# Op-amp_Microphone_Preamp.net
KiCad netlist of a schematic drawn in EAGLE
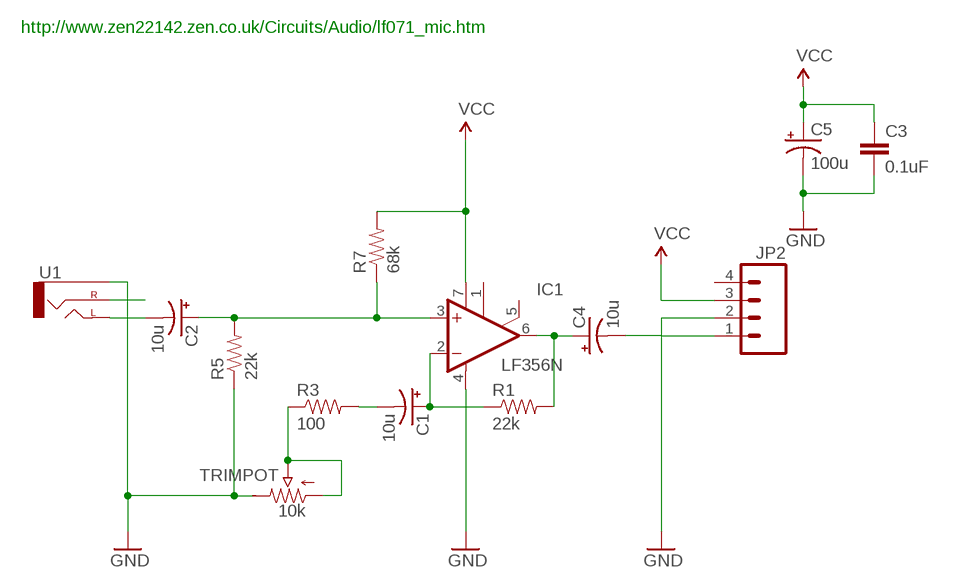
[diagram p0: schematic, sheet 1]

(export (version "E")
  (design (tool "Eeschema 10.0.6"))
  (components
    (comp (ref "C1")
      (value "10u")
      (footprint "eagle-import:CPOL-RADIAL-100UF-25V")
      (libsource (lib "eagle-import") (part "CAP_POLPTH1"))
    )
    (comp (ref "C2")
      (value "10u")
      (footprint "eagle-import:CPOL-RADIAL-100UF-25V")
      (libsource (lib "eagle-import") (part "CAP_POLPTH1"))
    )
    (comp (ref "C3")
      (value "0.1uF")
      (footprint "eagle-import:CAP-PTH-SMALL")
      (libsource (lib "eagle-import") (part "CAPPTH"))
    )
    (comp (ref "C4")
      (value "10u")
      (footprint "eagle-import:CPOL-RADIAL-100UF-25V")
      (libsource (lib "eagle-import") (part "CAP_POLPTH1"))
    )
    (comp (ref "C5")
      (value "100u")
      (footprint "eagle-import:CPOL-RADIAL-100UF-25V")
      (libsource (lib "eagle-import") (part "CAP_POLPTH1"))
    )
    (comp (ref "IC1")
      (value "LF356N")
      (footprint "eagle-import:DIL08")
      (libsource (lib "eagle-import") (part "LF356N"))
    )
    (comp (ref "JP2")
      (value "M04POLAR")
      (footprint "eagle-import:MOLEX-1X4")
      (libsource (lib "eagle-import") (part "M04POLAR"))
    )
    (comp (ref "R1")
      (value "22k")
      (footprint "eagle-import:1_6W-RES")
      (libsource (lib "eagle-import") (part "RESISTORPTH-1/6W"))
    )
    (comp (ref "R3")
      (value "100")
      (footprint "eagle-import:1_6W-RES")
      (libsource (lib "eagle-import") (part "SparkFun_RESISTORPTH-1/6W"))
    )
    (comp (ref "R5")
      (value "22k")
      (footprint "eagle-import:1_6W-RES")
      (libsource (lib "eagle-import") (part "SparkFun_RESISTORPTH-1/6W"))
    )
    (comp (ref "R7")
      (value "68k")
      (footprint "eagle-import:1_6W-RES")
      (libsource (lib "eagle-import") (part "SparkFun_RESISTORPTH-1/6W"))
    )
    (comp (ref "TRIMPOT")
      (value "10k")
      (footprint "eagle-import:3362U")
      (libsource (lib "eagle-import") (part "POT100K_3362U"))
    )
    (comp (ref "U1")
      (value "AUDIO-JACKPTH")
      (footprint "eagle-import:AUDIO-JACK")
      (libsource (lib "eagle-import") (part "AUDIO-JACKPTH"))
    )
  )
  (nets
    (net (code "1") (name "GND") (class "Default")
      (node (ref "C3") (pin "2") (pinfunction "2_2") (pintype "passive"))
      (node (ref "C5") (pin "2") (pinfunction "-_2") (pintype "passive"))
      (node (ref "IC1") (pin "4") (pinfunction "V-_4") (pintype "power_in"))
      (node (ref "JP2") (pin "2") (pinfunction "2_2") (pintype "passive"))
      (node (ref "R5") (pin "1") (pinfunction "1_1") (pintype "passive"))
      (node (ref "TRIMPOT") (pin "P$1") (pinfunction "E_P$1") (pintype "passive"))
      (node (ref "U1") (pin "SLEEVE") (pinfunction "SLEEVE_SLEEVE") (pintype "bidirectional"))
    )
    (net (code "2") (name "Net-(C1-+)") (class "Default")
      (node (ref "C1") (pin "1") (pinfunction "+_1") (pintype "passive"))
      (node (ref "IC1") (pin "2") (pinfunction "-IN_2") (pintype "input"))
      (node (ref "R1") (pin "1") (pinfunction "1_1") (pintype "passive"))
    )
    (net (code "3") (name "Net-(C1--)") (class "Default")
      (node (ref "C1") (pin "2") (pinfunction "-_2") (pintype "passive"))
      (node (ref "R3") (pin "2") (pinfunction "2_2") (pintype "passive"))
    )
    (net (code "4") (name "Net-(C2-+)") (class "Default")
      (node (ref "C2") (pin "1") (pinfunction "+_1") (pintype "passive"))
      (node (ref "IC1") (pin "3") (pinfunction "+IN_3") (pintype "input"))
      (node (ref "R5") (pin "2") (pinfunction "2_2") (pintype "passive"))
      (node (ref "R7") (pin "1") (pinfunction "1_1") (pintype "passive"))
    )
    (net (code "5") (name "Net-(C2--)") (class "Default")
      (node (ref "C2") (pin "2") (pinfunction "-_2") (pintype "passive"))
      (node (ref "U1") (pin "TIP") (pinfunction "LEFT_TIP") (pintype "bidirectional"))
    )
    (net (code "6") (name "Net-(C4-+)") (class "Default")
      (node (ref "C4") (pin "1") (pinfunction "+_1") (pintype "passive"))
      (node (ref "IC1") (pin "6") (pinfunction "OUT_6") (pintype "output"))
      (node (ref "R1") (pin "2") (pinfunction "2_2") (pintype "passive"))
    )
    (net (code "7") (name "Net-(C4--)") (class "Default")
      (node (ref "C4") (pin "2") (pinfunction "-_2") (pintype "passive"))
      (node (ref "JP2") (pin "1") (pinfunction "1_1") (pintype "passive"))
    )
    (net (code "8") (name "Net-(TRIMPOT-A)") (class "Default")
      (node (ref "R3") (pin "1") (pinfunction "1_1") (pintype "passive"))
      (node (ref "TRIMPOT") (pin "P$2") (pinfunction "S_P$2") (pintype "passive"))
      (node (ref "TRIMPOT") (pin "P$3") (pinfunction "A_P$3") (pintype "passive"))
    )
    (net (code "9") (name "VCC") (class "Default")
      (node (ref "C3") (pin "1") (pinfunction "1_1") (pintype "passive"))
      (node (ref "C5") (pin "1") (pinfunction "+_1") (pintype "passive"))
      (node (ref "IC1") (pin "7") (pinfunction "V+_7") (pintype "power_in"))
      (node (ref "JP2") (pin "3") (pinfunction "3_3") (pintype "passive"))
      (node (ref "R7") (pin "2") (pinfunction "2_2") (pintype "passive"))
    )
    (net (code "10") (name "unconnected-(IC1-BALANCE1-Pad1)") (class "Default")
      (node (ref "IC1") (pin "1") (pinfunction "BALANCE1_1") (pintype "passive"))
    )
    (net (code "11") (name "unconnected-(IC1-BALANCE2-Pad5)") (class "Default")
      (node (ref "IC1") (pin "5") (pinfunction "BALANCE2_5") (pintype "passive"))
    )
    (net (code "12") (name "unconnected-(JP2-Pad4)") (class "Default")
      (node (ref "JP2") (pin "4") (pinfunction "4_4") (pintype "passive"))
    )
    (net (code "13") (name "unconnected-(U1-RIGHT-PadRING)") (class "Default")
      (node (ref "U1") (pin "RING") (pinfunction "RIGHT_RING") (pintype "bidirectional"))
    )
  )
)
